# Programming.net
KiCad netlist of a schematic drawn in Altium Designer
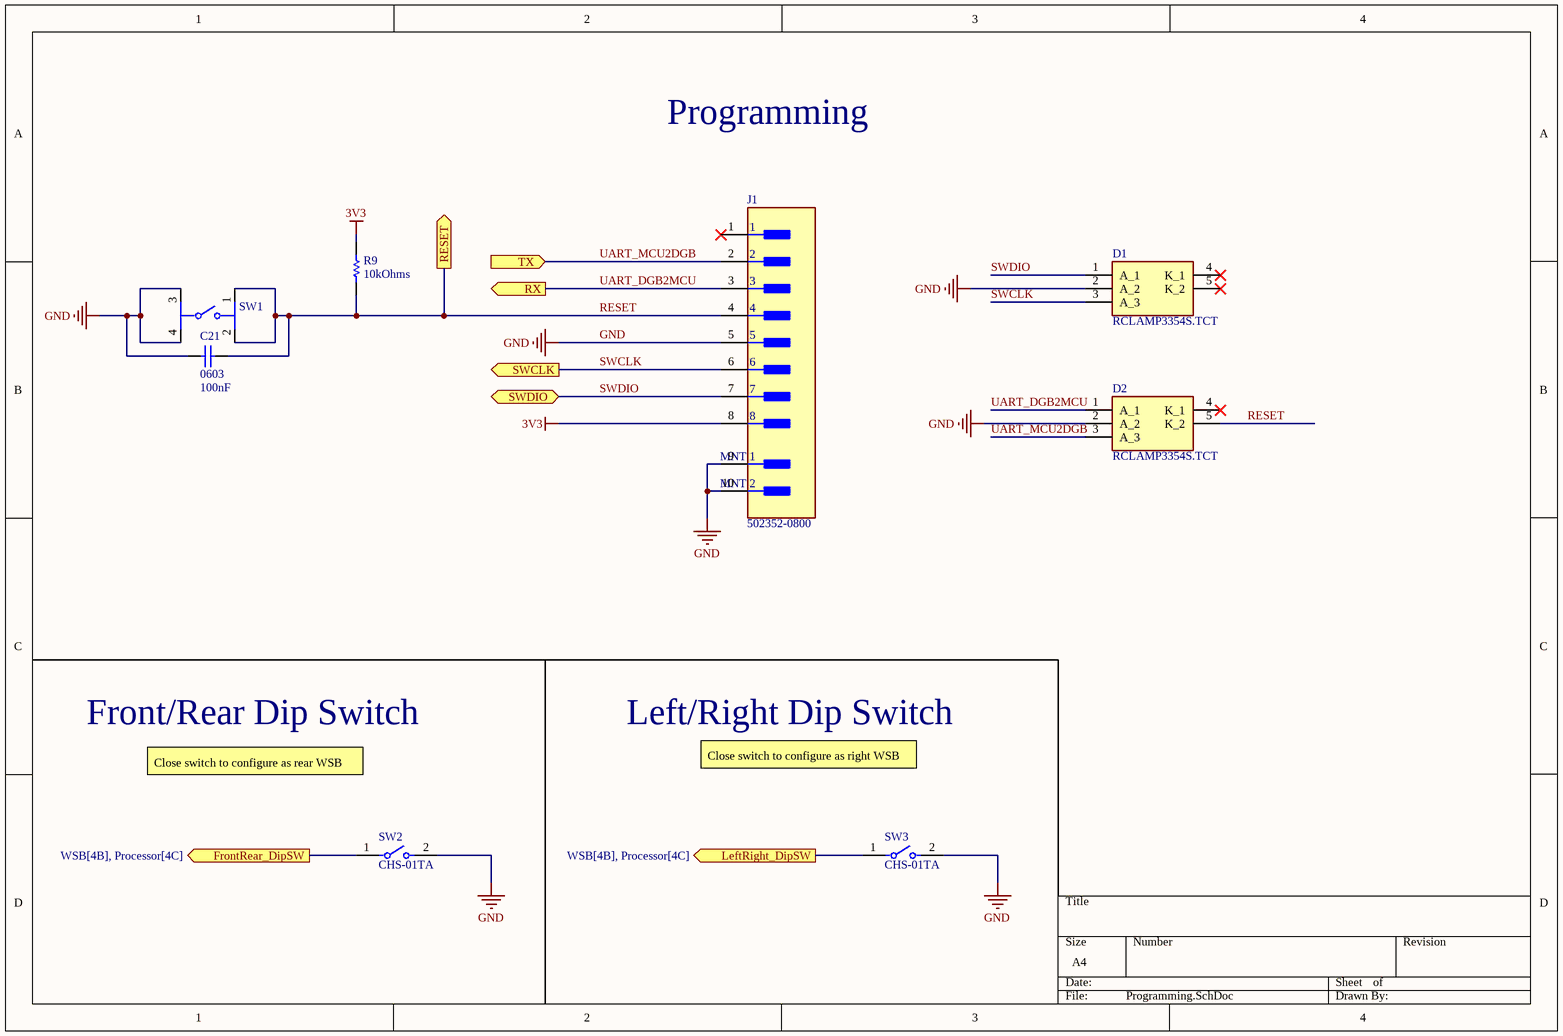
[diagram p0: Programming.SchDoc]

(export (version "E")
  (design (tool "Eeschema 10.0.6"))
  (components
    (comp (ref "C21")
      (value "C0603X104K5RACTU")
      (footprint "CAPC1608X87X35NL15T15")
      (fields
        (field (name "MANUFACTURER") "Kemet")
        (field (name "CASE CODE (IMPERIAL)") "0603")
        (field (name "CAPACITANCE") "100nF")
        (field (name "TOLERANCE") "10%")
        (field (name "VOLTAGE") "50V")
      )
      (libsource (lib "Altium Content Vault") (part "CAP"))
    )
    (comp (ref "D1")
      (value "RCLAMP3354S.TCT")
      (footprint "SamacSys:SOT95P280X145-5N")
      (description "TVS Diode (Bi-directional)")
      (fields (field (name "MOUSER PART NUMBER") "947-RCLAMP3354S.TCT"))
      (libsource (lib "*") (part "RCLAMP3354S.TCT"))
    )
    (comp (ref "D2")
      (value "RCLAMP3354S.TCT")
      (footprint "SamacSys:SOT95P280X145-5N")
      (description "TVS Diode (Bi-directional)")
      (fields (field (name "MOUSER PART NUMBER") "947-RCLAMP3354S.TCT"))
      (libsource (lib "*") (part "RCLAMP3354S.TCT"))
    )
    (comp (ref "J1")
      (value "502352-0800")
      (footprint "FP-502352-0800-MFG")
      (description "CONN HEADER SMD R/A 8POS 2MM")
      (libsource (lib "Altium Content Vault") (part "98b5586d6b3804e276fbd0410cd4945"))
    )
    (comp (ref "R9")
      (value "RC0603JR-0710KL")
      (footprint "RESC1608X55X25ML10T15")
      (description "Resistor, 10 KOhm, +/- 5%, 100 mW, -55 to 155 degC, 0603 (1608 Metric), RoHS, Tape and Reel")
      (fields
        (field (name "RESISTANCE") "10kOhms")
        (field (name "MANUFACTURER") "Yageo")
        (field (name "TOLERANCE") "5%")
      )
      (libsource (lib "Altium Content Vault") (part "RES-2"))
    )
    (comp (ref "SW1")
      (value "PTS645SM43SMTR92LFS")
      (footprint "FP-PTS645SM43SMTR92LFS-MFG")
      (description "SWITCH TACTILE SPST-NO 0.05A 12V")
      (libsource (lib "Altium Content Vault") (part "1adf0dd01260c80cf25a44bfd6b99ba"))
    )
    (comp (ref "SW2")
      (value "CHS-01TA")
      (footprint "FP-CHS-01TA-MFG")
      (description "SWITCH SLIDE DIP SPST 100MA 6V")
      (fields
        (field (name "OCTOPART") "https://octopart.com/chs-01ta-nidec+copal-52304644")
        (field (name "MANUFACTURER") "Nidec Copal Electronics")
      )
      (libsource (lib "Altium Content Vault") (part "bb27bde45df87f1f469753f287ef5ae"))
    )
    (comp (ref "SW3")
      (value "CHS-01TA")
      (footprint "FP-CHS-01TA-MFG")
      (description "SWITCH SLIDE DIP SPST 100MA 6V")
      (fields
        (field (name "OCTOPART") "https://octopart.com/chs-01ta-nidec+copal-52304644")
        (field (name "MANUFACTURER") "Nidec Copal Electronics")
      )
      (libsource (lib "Altium Content Vault") (part "bb27bde45df87f1f469753f287ef5ae"))
    )
  )
  (nets
    (net (code "1") (name "/FrontRear_DipSW") (class "Default")
      (node (ref "SW2") (pin "1") (pinfunction "1_1") (pintype "passive"))
    )
    (net (code "2") (name "/LeftRight_DipSW") (class "Default")
      (node (ref "SW3") (pin "1") (pinfunction "1_1") (pintype "passive"))
    )
    (net (code "3") (name "/RESET") (class "Default")
      (node (ref "C21") (pin "1") (pinfunction "1_1") (pintype "passive"))
      (node (ref "D2") (pin "5") (pinfunction "K_2_5") (pintype "passive"))
      (node (ref "J1") (pin "4") (pinfunction "4_4") (pintype "passive"))
      (node (ref "R9") (pin "1") (pinfunction "1_1") (pintype "passive"))
      (node (ref "SW1") (pin "1") (pinfunction "1_1") (pintype "passive"))
      (node (ref "SW1") (pin "2") (pinfunction "2_2") (pintype "passive"))
    )
    (net (code "4") (name "/SWCLK") (class "Default")
      (node (ref "D1") (pin "3") (pinfunction "A_3_3") (pintype "passive"))
      (node (ref "J1") (pin "6") (pinfunction "6_6") (pintype "passive"))
    )
    (net (code "5") (name "/SWDIO") (class "Default")
      (node (ref "D1") (pin "1") (pinfunction "A_1_1") (pintype "passive"))
      (node (ref "J1") (pin "7") (pinfunction "7_7") (pintype "passive"))
    )
    (net (code "6") (name "/UART_DGB2MCU") (class "Default")
      (node (ref "D2") (pin "1") (pinfunction "A_1_1") (pintype "passive"))
      (node (ref "J1") (pin "3") (pinfunction "3_3") (pintype "passive"))
    )
    (net (code "7") (name "/UART_MCU2DGB") (class "Default")
      (node (ref "D2") (pin "3") (pinfunction "A_3_3") (pintype "passive"))
      (node (ref "J1") (pin "2") (pinfunction "2_2") (pintype "passive"))
    )
    (net (code "8") (name "3V3") (class "Default")
      (node (ref "J1") (pin "8") (pinfunction "8_8") (pintype "passive"))
      (node (ref "R9") (pin "2") (pinfunction "2_2") (pintype "passive"))
    )
    (net (code "9") (name "GND") (class "Default")
      (node (ref "C21") (pin "2") (pinfunction "2_2") (pintype "passive"))
      (node (ref "D1") (pin "2") (pinfunction "A_2_2") (pintype "passive"))
      (node (ref "D2") (pin "2") (pinfunction "A_2_2") (pintype "passive"))
      (node (ref "J1") (pin "10") (pinfunction "MNT_2_10") (pintype "passive"))
      (node (ref "J1") (pin "5") (pinfunction "5_5") (pintype "passive"))
      (node (ref "J1") (pin "9") (pinfunction "MNT_1_9") (pintype "passive"))
      (node (ref "SW1") (pin "3") (pinfunction "3_3") (pintype "passive"))
      (node (ref "SW1") (pin "4") (pinfunction "4_4") (pintype "passive"))
      (node (ref "SW2") (pin "2") (pinfunction "2_2") (pintype "passive"))
      (node (ref "SW3") (pin "2") (pinfunction "2_2") (pintype "passive"))
    )
    (net (code "10") (name "unconnected-(D1-K_1-Pad4)") (class "Default")
      (node (ref "D1") (pin "4") (pinfunction "K_1_4") (pintype "passive+no_connect"))
    )
    (net (code "11") (name "unconnected-(D1-K_2-Pad5)") (class "Default")
      (node (ref "D1") (pin "5") (pinfunction "K_2_5") (pintype "passive+no_connect"))
    )
    (net (code "12") (name "unconnected-(D2-K_1-Pad4)") (class "Default")
      (node (ref "D2") (pin "4") (pinfunction "K_1_4") (pintype "passive+no_connect"))
    )
    (net (code "13") (name "unconnected-(J1-Pad1)") (class "Default")
      (node (ref "J1") (pin "1") (pinfunction "1_1") (pintype "passive+no_connect"))
    )
  )
)
